# THREE.net
KiCad netlist of a schematic drawn in EAGLE
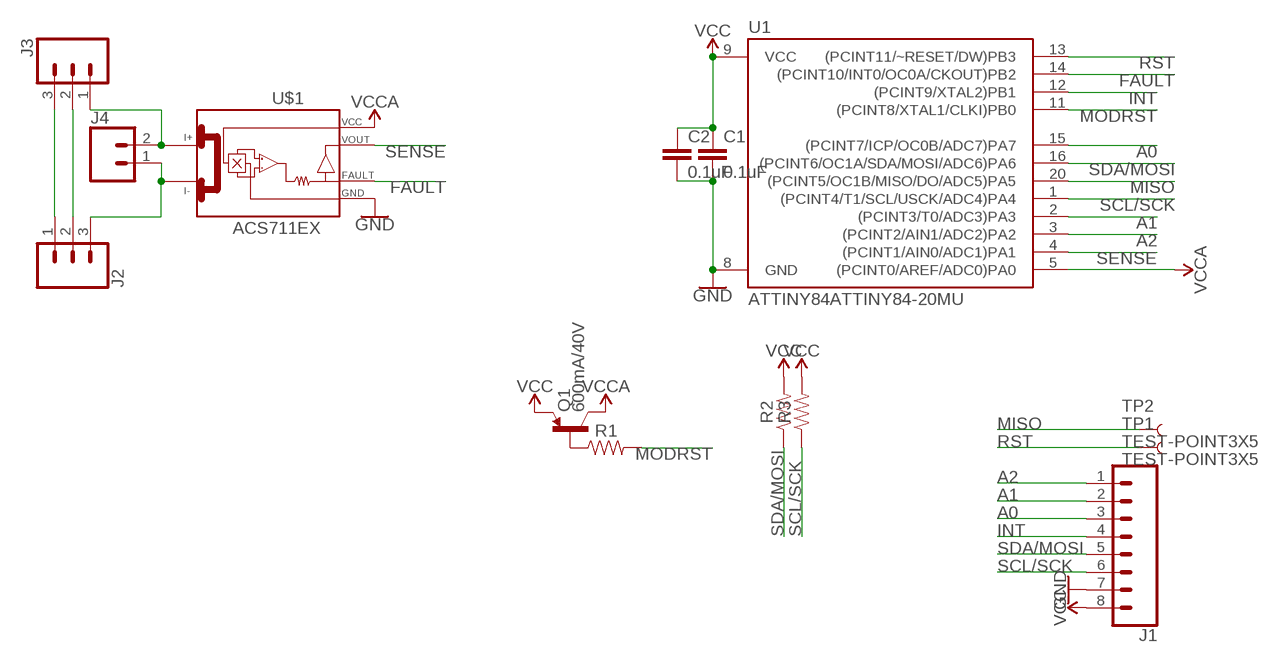
[diagram p0: schematic, sheet 1]

(export (version "E")
  (design (tool "Eeschema 10.0.6"))
  (components
    (comp (ref "C1")
      (value "0.1uF")
      (footprint "eagle-import:0603")
      (libsource (lib "eagle-import") (part "0.1UF-0603-25V-5%"))
    )
    (comp (ref "C2")
      (value "0.1uF")
      (footprint "eagle-import:0603")
      (libsource (lib "eagle-import") (part "0.1UF-0603-25V-5%"))
    )
    (comp (ref "J1")
      (value "CONN_08NO_SILK_FEMALE_PTH")
      (footprint "eagle-import:1X08_NO_SILK")
      (libsource (lib "eagle-import") (part "CONN_08NO_SILK_FEMALE_PTH"))
    )
    (comp (ref "J2")
      (value "CONN_03-SCREW-5MM")
      (footprint "eagle-import:SCREWTERMINAL-5MM-3")
      (libsource (lib "eagle-import") (part "CONN_03-SCREW-5MM"))
    )
    (comp (ref "J3")
      (value "CONN_03-SCREW-5MM")
      (footprint "eagle-import:SCREWTERMINAL-5MM-3")
      (libsource (lib "eagle-import") (part "CONN_03-SCREW-5MM"))
    )
    (comp (ref "J4")
      (value "CONN_02")
      (footprint "eagle-import:1X02")
      (libsource (lib "eagle-import") (part "CONN_02"))
    )
    (comp (ref "Q1")
      (value "600mA/40V")
      (footprint "eagle-import:SOT23-3")
      (libsource (lib "eagle-import") (part "TRANS_PNP-MMBT4403"))
    )
    (comp (ref "R1")
      (value "RESISTOR0603")
      (footprint "eagle-import:0603")
      (libsource (lib "eagle-import") (part "RESISTOR0603"))
    )
    (comp (ref "R2")
      (value "RESISTOR0603")
      (footprint "eagle-import:0603")
      (libsource (lib "eagle-import") (part "RESISTOR0603"))
    )
    (comp (ref "R3")
      (value "RESISTOR0603")
      (footprint "eagle-import:0603")
      (libsource (lib "eagle-import") (part "RESISTOR0603"))
    )
    (comp (ref "TP1")
      (value "TEST-POINT3X5")
      (footprint "eagle-import:PAD.03X.05")
      (libsource (lib "eagle-import") (part "TEST-POINT3X5"))
    )
    (comp (ref "TP2")
      (value "TEST-POINT3X5")
      (footprint "eagle-import:PAD.03X.05")
      (libsource (lib "eagle-import") (part "TEST-POINT3X5"))
    )
    (comp (ref "U$1")
      (value "ACS711EX")
      (footprint "eagle-import:QFN-12EX_3X3")
      (libsource (lib "eagle-import") (part "ACS711EX"))
    )
    (comp (ref "U1")
      (value "ATTINY84ATTINY84-20MU")
      (footprint "eagle-import:QFN20")
      (libsource (lib "eagle-import") (part "ATTINY84ATTINY84-20MU"))
    )
  )
  (nets
    (net (code "1") (name "/A0") (class "Default")
      (node (ref "J1") (pin "3") (pinfunction "3_3") (pintype "passive"))
      (node (ref "U1") (pin "15") (pinfunction "(PCINT7/ICP/OC0B/ADC7)PA7_15") (pintype "bidirectional"))
    )
    (net (code "2") (name "/A1") (class "Default")
      (node (ref "J1") (pin "2") (pinfunction "2_2") (pintype "passive"))
      (node (ref "U1") (pin "2") (pinfunction "(PCINT3/T0/ADC3)PA3_2") (pintype "bidirectional"))
    )
    (net (code "3") (name "/A2") (class "Default")
      (node (ref "J1") (pin "1") (pinfunction "1_1") (pintype "passive"))
      (node (ref "U1") (pin "3") (pinfunction "(PCINT2/AIN1/ADC2)PA2_3") (pintype "bidirectional"))
    )
    (net (code "4") (name "/FAULT") (class "Default")
      (node (ref "U$1") (pin "P$4") (pinfunction "FAULT_P$4") (pintype "bidirectional"))
      (node (ref "U1") (pin "14") (pinfunction "(PCINT10/INT0/OC0A/CKOUT)PB2_14") (pintype "bidirectional"))
    )
    (net (code "5") (name "/INT") (class "Default")
      (node (ref "J1") (pin "4") (pinfunction "4_4") (pintype "passive"))
      (node (ref "U1") (pin "12") (pinfunction "(PCINT9/XTAL2)PB1_12") (pintype "bidirectional"))
    )
    (net (code "6") (name "/MISO") (class "Default")
      (node (ref "TP2") (pin "P$1") (pinfunction "1_P$1") (pintype "bidirectional"))
      (node (ref "U1") (pin "20") (pinfunction "(PCINT5/OC1B/MISO/DO/ADC5)PA5_20") (pintype "bidirectional"))
    )
    (net (code "7") (name "/MODRST") (class "Default")
      (node (ref "R1") (pin "2") (pinfunction "2_2") (pintype "passive"))
      (node (ref "U1") (pin "11") (pinfunction "(PCINT8/XTAL1/CLKI)PB0_11") (pintype "bidirectional"))
    )
    (net (code "8") (name "/RST") (class "Default")
      (node (ref "TP1") (pin "P$1") (pinfunction "1_P$1") (pintype "bidirectional"))
      (node (ref "U1") (pin "13") (pinfunction "(PCINT11/~{RESET/DW})PB3_13") (pintype "bidirectional"))
    )
    (net (code "9") (name "/SCL{slash}SCK") (class "Default")
      (node (ref "J1") (pin "6") (pinfunction "6_6") (pintype "passive"))
      (node (ref "R3") (pin "1") (pinfunction "1_1") (pintype "passive"))
      (node (ref "U1") (pin "1") (pinfunction "(PCINT4/T1/SCL/USCK/ADC4)PA4_1") (pintype "bidirectional"))
    )
    (net (code "10") (name "/SDA{slash}MOSI") (class "Default")
      (node (ref "J1") (pin "5") (pinfunction "5_5") (pintype "passive"))
      (node (ref "R2") (pin "1") (pinfunction "1_1") (pintype "passive"))
      (node (ref "U1") (pin "16") (pinfunction "(PCINT6/OC1A/SDA/MOSI/ADC6)PA6_16") (pintype "bidirectional"))
    )
    (net (code "11") (name "/SENSE") (class "Default")
      (node (ref "U$1") (pin "P$9") (pinfunction "VOUT_P$9") (pintype "output"))
      (node (ref "U1") (pin "4") (pinfunction "(PCINT1/AIN0/ADC1)PA1_4") (pintype "bidirectional"))
    )
    (net (code "12") (name "GND") (class "Default")
      (node (ref "C1") (pin "2") (pinfunction "2_2") (pintype "passive"))
      (node (ref "C2") (pin "2") (pinfunction "2_2") (pintype "passive"))
      (node (ref "J1") (pin "7") (pinfunction "7_7") (pintype "passive"))
      (node (ref "U$1") (pin "P$3") (pinfunction "GND_P$3") (pintype "power_in"))
      (node (ref "U1") (pin "8") (pinfunction "GND_8") (pintype "bidirectional"))
    )
    (net (code "13") (name "Net-(J2-Pad1)") (class "Default")
      (node (ref "J2") (pin "1") (pinfunction "1_1") (pintype "passive"))
      (node (ref "J3") (pin "3") (pinfunction "3_3") (pintype "passive"))
    )
    (net (code "14") (name "Net-(J2-Pad2)") (class "Default")
      (node (ref "J2") (pin "2") (pinfunction "2_2") (pintype "passive"))
      (node (ref "J3") (pin "2") (pinfunction "2_2") (pintype "passive"))
    )
    (net (code "15") (name "Net-(Q1-B)") (class "Default")
      (node (ref "Q1") (pin "1") (pinfunction "B_1") (pintype "passive"))
      (node (ref "R1") (pin "1") (pinfunction "1_1") (pintype "passive"))
    )
    (net (code "16") (name "Net-(U$1-I+_1)") (class "Default")
      (node (ref "J3") (pin "1") (pinfunction "1_1") (pintype "passive"))
      (node (ref "J4") (pin "2") (pinfunction "2_2") (pintype "passive"))
      (node (ref "U$1") (pin "P$1") (pinfunction "I+_1_P$1") (pintype "bidirectional"))
    )
    (net (code "17") (name "Net-(U$1-I-_1)") (class "Default")
      (node (ref "J2") (pin "3") (pinfunction "3_3") (pintype "passive"))
      (node (ref "J4") (pin "1") (pinfunction "1_1") (pintype "passive"))
      (node (ref "U$1") (pin "P$2") (pinfunction "I-_1_P$2") (pintype "bidirectional"))
    )
    (net (code "18") (name "VCC") (class "Default")
      (node (ref "C1") (pin "1") (pinfunction "1_1") (pintype "passive"))
      (node (ref "C2") (pin "1") (pinfunction "1_1") (pintype "passive"))
      (node (ref "J1") (pin "8") (pinfunction "8_8") (pintype "passive"))
      (node (ref "Q1") (pin "2") (pinfunction "E_2") (pintype "passive"))
      (node (ref "R2") (pin "2") (pinfunction "2_2") (pintype "passive"))
      (node (ref "R3") (pin "2") (pinfunction "2_2") (pintype "passive"))
      (node (ref "U1") (pin "9") (pinfunction "VCC_9") (pintype "bidirectional"))
    )
    (net (code "19") (name "VCCA") (class "Default")
      (node (ref "Q1") (pin "3") (pinfunction "C_3") (pintype "passive"))
      (node (ref "U$1") (pin "P$10") (pinfunction "VCC_P$10") (pintype "power_in"))
      (node (ref "U1") (pin "5") (pinfunction "(PCINT0/AREF/ADC0)PA0_5") (pintype "bidirectional"))
    )
  )
)
